# Wifi_Topside_Adapter_0_1.net
KiCad netlist of a schematic drawn in EAGLE
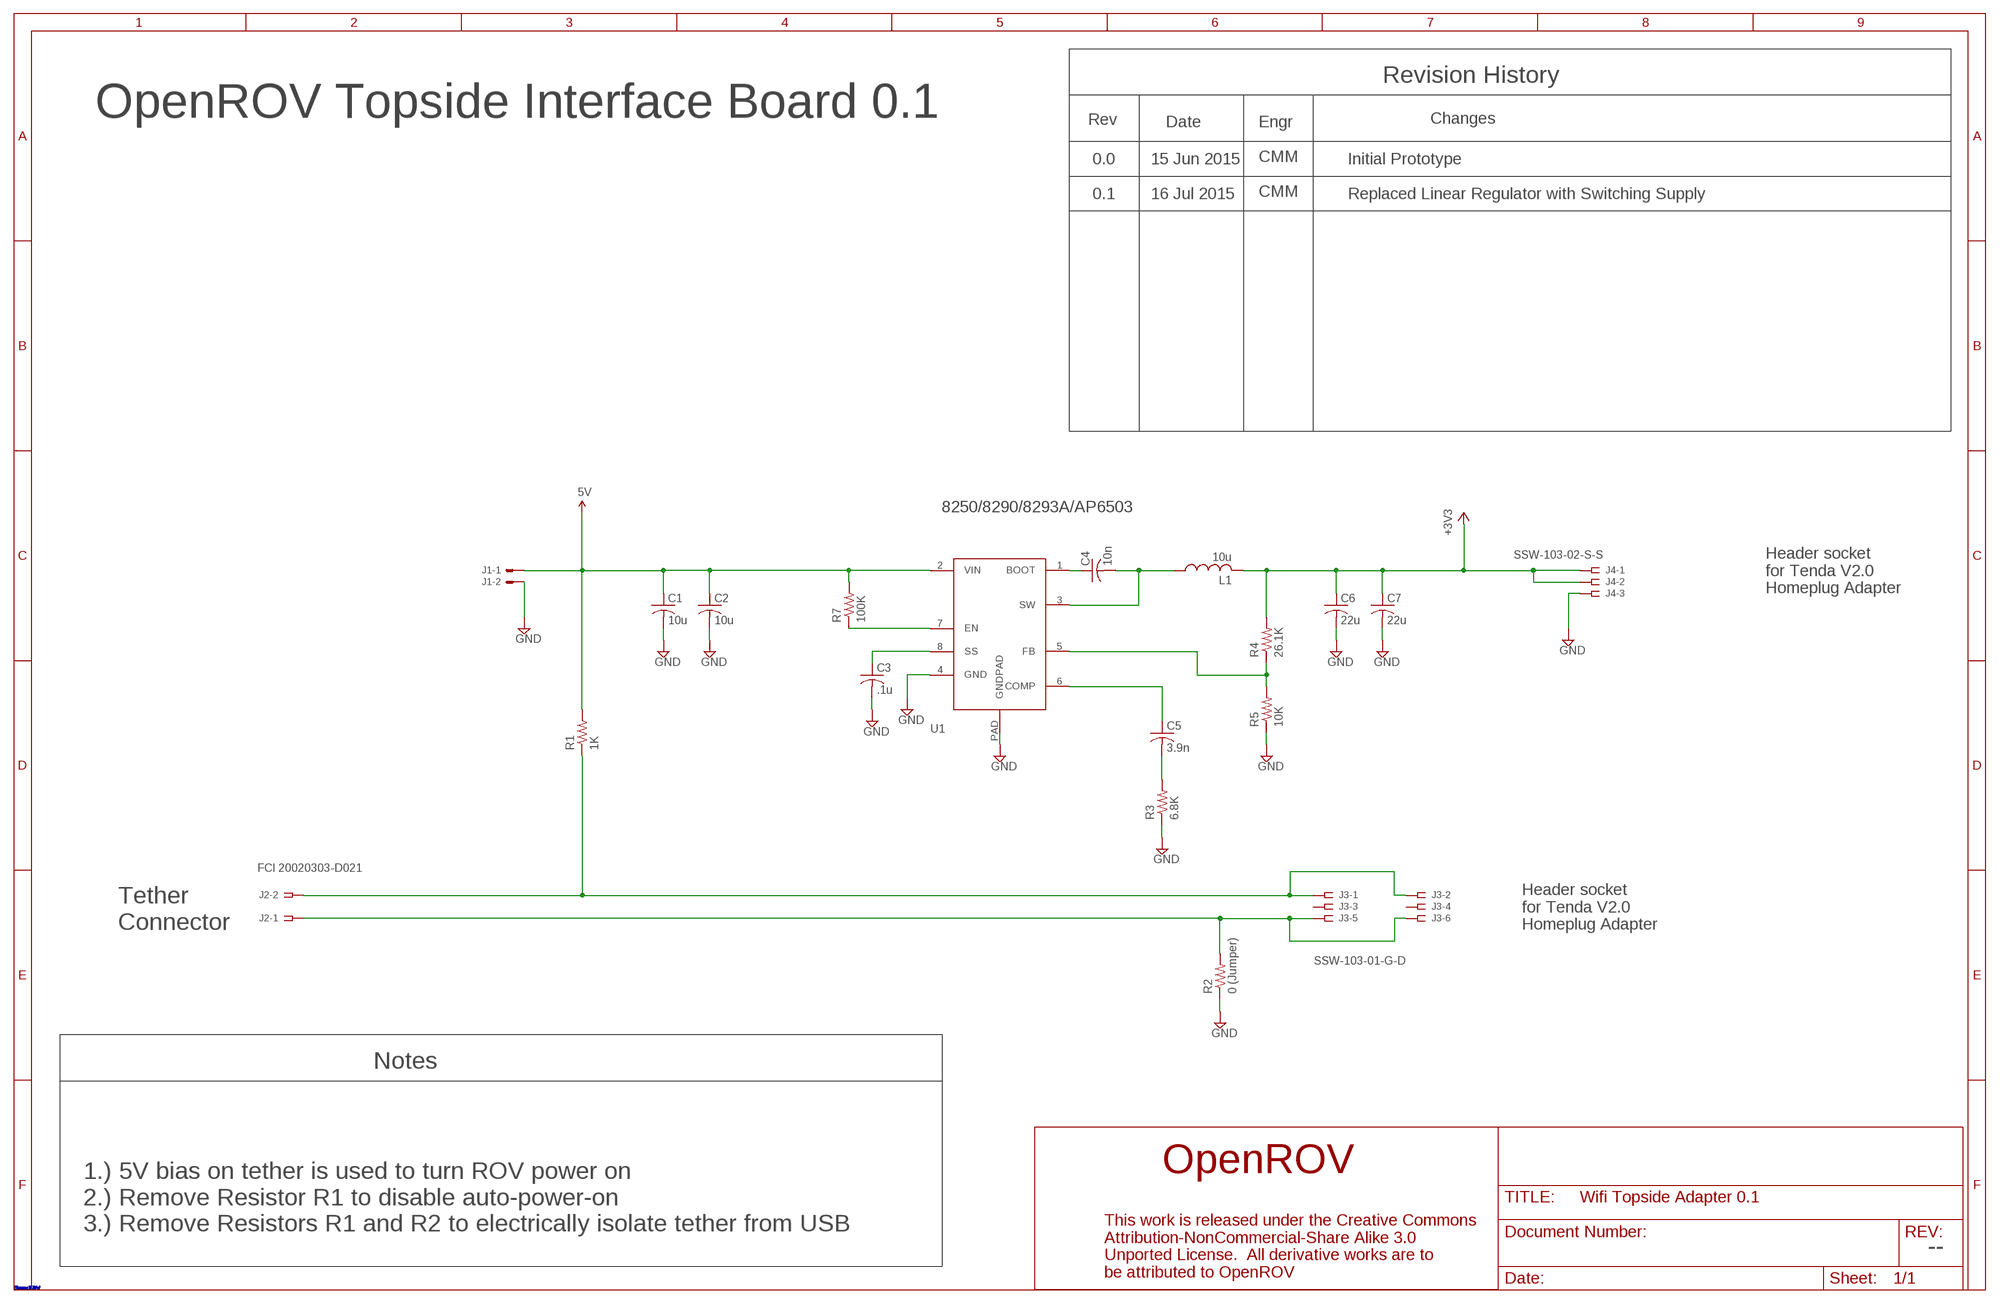
[diagram p0: schematic, sheet 1]

(export (version "E")
  (design (tool "Eeschema 10.0.6"))
  (components
    (comp (ref "C1")
      (value "10u")
      (footprint "eagle-import:R1206")
      (libsource (lib "eagle-import") (part "CAP1206"))
    )
    (comp (ref "C2")
      (value "10u")
      (footprint "eagle-import:R1206")
      (libsource (lib "eagle-import") (part "CAP1206"))
    )
    (comp (ref "C3")
      (value ".1u")
      (footprint "eagle-import:R0805")
      (libsource (lib "eagle-import") (part "CAP0805"))
    )
    (comp (ref "C4")
      (value "10n")
      (footprint "eagle-import:R0805")
      (libsource (lib "eagle-import") (part "CAP0805"))
    )
    (comp (ref "C5")
      (value "3.9n")
      (footprint "eagle-import:R0805")
      (libsource (lib "eagle-import") (part "CAP0805"))
    )
    (comp (ref "C6")
      (value "22u")
      (footprint "eagle-import:R1206")
      (libsource (lib "eagle-import") (part "CAP1206"))
    )
    (comp (ref "C7")
      (value "22u")
      (footprint "eagle-import:R1206")
      (libsource (lib "eagle-import") (part "CAP1206"))
    )
    (comp (ref "J1")
      (value "HDR_1X2X0.100-ALT_SILK")
      (footprint "eagle-import:22-23-2021_ALT_SILK")
      (libsource (lib "eagle-import") (part "HDR_1X2X0.100-ALT_SILK"))
    )
    (comp (ref "J2")
      (value "FCI 20020303-D021")
      (footprint "eagle-import:FCI_09-381_2PL")
      (libsource (lib "eagle-import") (part "FCI_TERMINAL_BLOCK_2PL"))
    )
    (comp (ref "J3")
      (value "SSW-103-01-G-D")
      (footprint "eagle-import:SSW-103-02-S-D")
      (fields (field (name "MPN") "SSW-103-02-S-D"))
      (libsource (lib "eagle-import") (part "HDR_SOCKET_2X3"))
    )
    (comp (ref "J4")
      (value "SSW-103-02-S-S")
      (footprint "eagle-import:SSW-103-02-S-S")
      (libsource (lib "eagle-import") (part "SSW-103-02-S-S"))
    )
    (comp (ref "L1")
      (value "10u")
      (footprint "eagle-import:INDUCTOR_3A_TEST")
      (libsource (lib "eagle-import") (part "INDUCTOR3A_TEST"))
    )
    (comp (ref "R1")
      (value "1K")
      (footprint "eagle-import:R0805")
      (libsource (lib "eagle-import") (part "RESISTOR-0805"))
    )
    (comp (ref "R2")
      (value "0 (Jumper)")
      (footprint "eagle-import:R0805")
      (libsource (lib "eagle-import") (part "RESISTOR-0805"))
    )
    (comp (ref "R3")
      (value "6.8K")
      (footprint "eagle-import:R0805")
      (libsource (lib "eagle-import") (part "RESISTOR-0805"))
    )
    (comp (ref "R4")
      (value "26.1K")
      (footprint "eagle-import:R0805")
      (libsource (lib "eagle-import") (part "RESISTOR-0805"))
    )
    (comp (ref "R5")
      (value "10K")
      (footprint "eagle-import:R0805")
      (libsource (lib "eagle-import") (part "RESISTOR-0805"))
    )
    (comp (ref "R7")
      (value "100K")
      (footprint "eagle-import:R0805")
      (libsource (lib "eagle-import") (part "RESISTOR-0805"))
    )
    (comp (ref "U1")
      (value "RICHTEK_82XX")
      (footprint "eagle-import:SO8-THERMAL")
      (libsource (lib "eagle-import") (part "RICHTEK_82XX"))
    )
  )
  (nets
    (net (code "1") (name "+3V3") (class "Default")
      (node (ref "C6") (pin "1") (pinfunction "1_1") (pintype "passive"))
      (node (ref "C7") (pin "1") (pinfunction "1_1") (pintype "passive"))
      (node (ref "J4") (pin "1") (pinfunction "1_1") (pintype "passive"))
      (node (ref "J4") (pin "2") (pinfunction "1_2") (pintype "passive"))
      (node (ref "L1") (pin "P$2") (pinfunction "2_P$2") (pintype "passive"))
      (node (ref "R4") (pin "2") (pinfunction "2_2") (pintype "passive"))
    )
    (net (code "2") (name "5V") (class "Default")
      (node (ref "C1") (pin "1") (pinfunction "1_1") (pintype "passive"))
      (node (ref "C2") (pin "1") (pinfunction "1_1") (pintype "passive"))
      (node (ref "J1") (pin "1") (pinfunction "S_1") (pintype "passive"))
      (node (ref "R1") (pin "2") (pinfunction "2_2") (pintype "passive"))
      (node (ref "R7") (pin "2") (pinfunction "2_2") (pintype "passive"))
      (node (ref "U1") (pin "2") (pinfunction "VIN_2") (pintype "bidirectional"))
    )
    (net (code "3") (name "GND") (class "Default")
      (node (ref "C1") (pin "2") (pinfunction "2_2") (pintype "passive"))
      (node (ref "C2") (pin "2") (pinfunction "2_2") (pintype "passive"))
      (node (ref "C3") (pin "2") (pinfunction "2_2") (pintype "passive"))
      (node (ref "C6") (pin "2") (pinfunction "2_2") (pintype "passive"))
      (node (ref "C7") (pin "2") (pinfunction "2_2") (pintype "passive"))
      (node (ref "J1") (pin "2") (pinfunction "S_2") (pintype "passive"))
      (node (ref "J4") (pin "3") (pinfunction "1_3") (pintype "passive"))
      (node (ref "R2") (pin "1") (pinfunction "1_1") (pintype "passive"))
      (node (ref "R3") (pin "1") (pinfunction "1_1") (pintype "passive"))
      (node (ref "R5") (pin "1") (pinfunction "1_1") (pintype "passive"))
      (node (ref "U1") (pin "4") (pinfunction "GND_4") (pintype "bidirectional"))
      (node (ref "U1") (pin "PAD") (pinfunction "GNDPAD_PAD") (pintype "bidirectional"))
    )
    (net (code "4") (name "Net-(C5-Pad2)") (class "Default")
      (node (ref "C5") (pin "2") (pinfunction "2_2") (pintype "passive"))
      (node (ref "R3") (pin "2") (pinfunction "2_2") (pintype "passive"))
    )
    (net (code "5") (name "Net-(J3B-1)") (class "Default")
      (node (ref "J2") (pin "2A") (pinfunction "1_2A") (pintype "passive"))
      (node (ref "J2") (pin "2B") (pinfunction "1_2B") (pintype "passive"))
      (node (ref "J3") (pin "1") (pinfunction "1_1") (pintype "passive"))
      (node (ref "J3") (pin "2") (pinfunction "1_2") (pintype "passive"))
      (node (ref "R1") (pin "1") (pinfunction "1_1") (pintype "passive"))
    )
    (net (code "6") (name "Net-(J3E-1)") (class "Default")
      (node (ref "J2") (pin "1A") (pinfunction "1_1A") (pintype "passive"))
      (node (ref "J2") (pin "1B") (pinfunction "1_1B") (pintype "passive"))
      (node (ref "J3") (pin "5") (pinfunction "1_5") (pintype "passive"))
      (node (ref "J3") (pin "6") (pinfunction "1_6") (pintype "passive"))
      (node (ref "R2") (pin "2") (pinfunction "2_2") (pintype "passive"))
    )
    (net (code "7") (name "Net-(L1-1)") (class "Default")
      (node (ref "C4") (pin "2") (pinfunction "2_2") (pintype "passive"))
      (node (ref "L1") (pin "P$1") (pinfunction "1_P$1") (pintype "passive"))
      (node (ref "U1") (pin "3") (pinfunction "SW_3") (pintype "bidirectional"))
    )
    (net (code "8") (name "Net-(U1-BOOT)") (class "Default")
      (node (ref "C4") (pin "1") (pinfunction "1_1") (pintype "passive"))
      (node (ref "U1") (pin "1") (pinfunction "BOOT_1") (pintype "bidirectional"))
    )
    (net (code "9") (name "Net-(U1-COMP)") (class "Default")
      (node (ref "C5") (pin "1") (pinfunction "1_1") (pintype "passive"))
      (node (ref "U1") (pin "6") (pinfunction "COMP_6") (pintype "bidirectional"))
    )
    (net (code "10") (name "Net-(U1-EN)") (class "Default")
      (node (ref "R7") (pin "1") (pinfunction "1_1") (pintype "passive"))
      (node (ref "U1") (pin "7") (pinfunction "EN_7") (pintype "bidirectional"))
    )
    (net (code "11") (name "Net-(U1-FB)") (class "Default")
      (node (ref "R4") (pin "1") (pinfunction "1_1") (pintype "passive"))
      (node (ref "R5") (pin "2") (pinfunction "2_2") (pintype "passive"))
      (node (ref "U1") (pin "5") (pinfunction "FB_5") (pintype "bidirectional"))
    )
    (net (code "12") (name "Net-(U1-SS)") (class "Default")
      (node (ref "C3") (pin "1") (pinfunction "1_1") (pintype "passive"))
      (node (ref "U1") (pin "8") (pinfunction "SS_8") (pintype "bidirectional"))
    )
    (net (code "13") (name "unconnected-(J3C-1-Pad3)") (class "Default")
      (node (ref "J3") (pin "3") (pinfunction "1_3") (pintype "passive"))
    )
    (net (code "14") (name "unconnected-(J3D-1-Pad4)") (class "Default")
      (node (ref "J3") (pin "4") (pinfunction "1_4") (pintype "passive"))
    )
  )
)
